# arduino-pro-mini_2-way-switches_v0_2_1.net
KiCad netlist of a schematic drawn in EAGLE
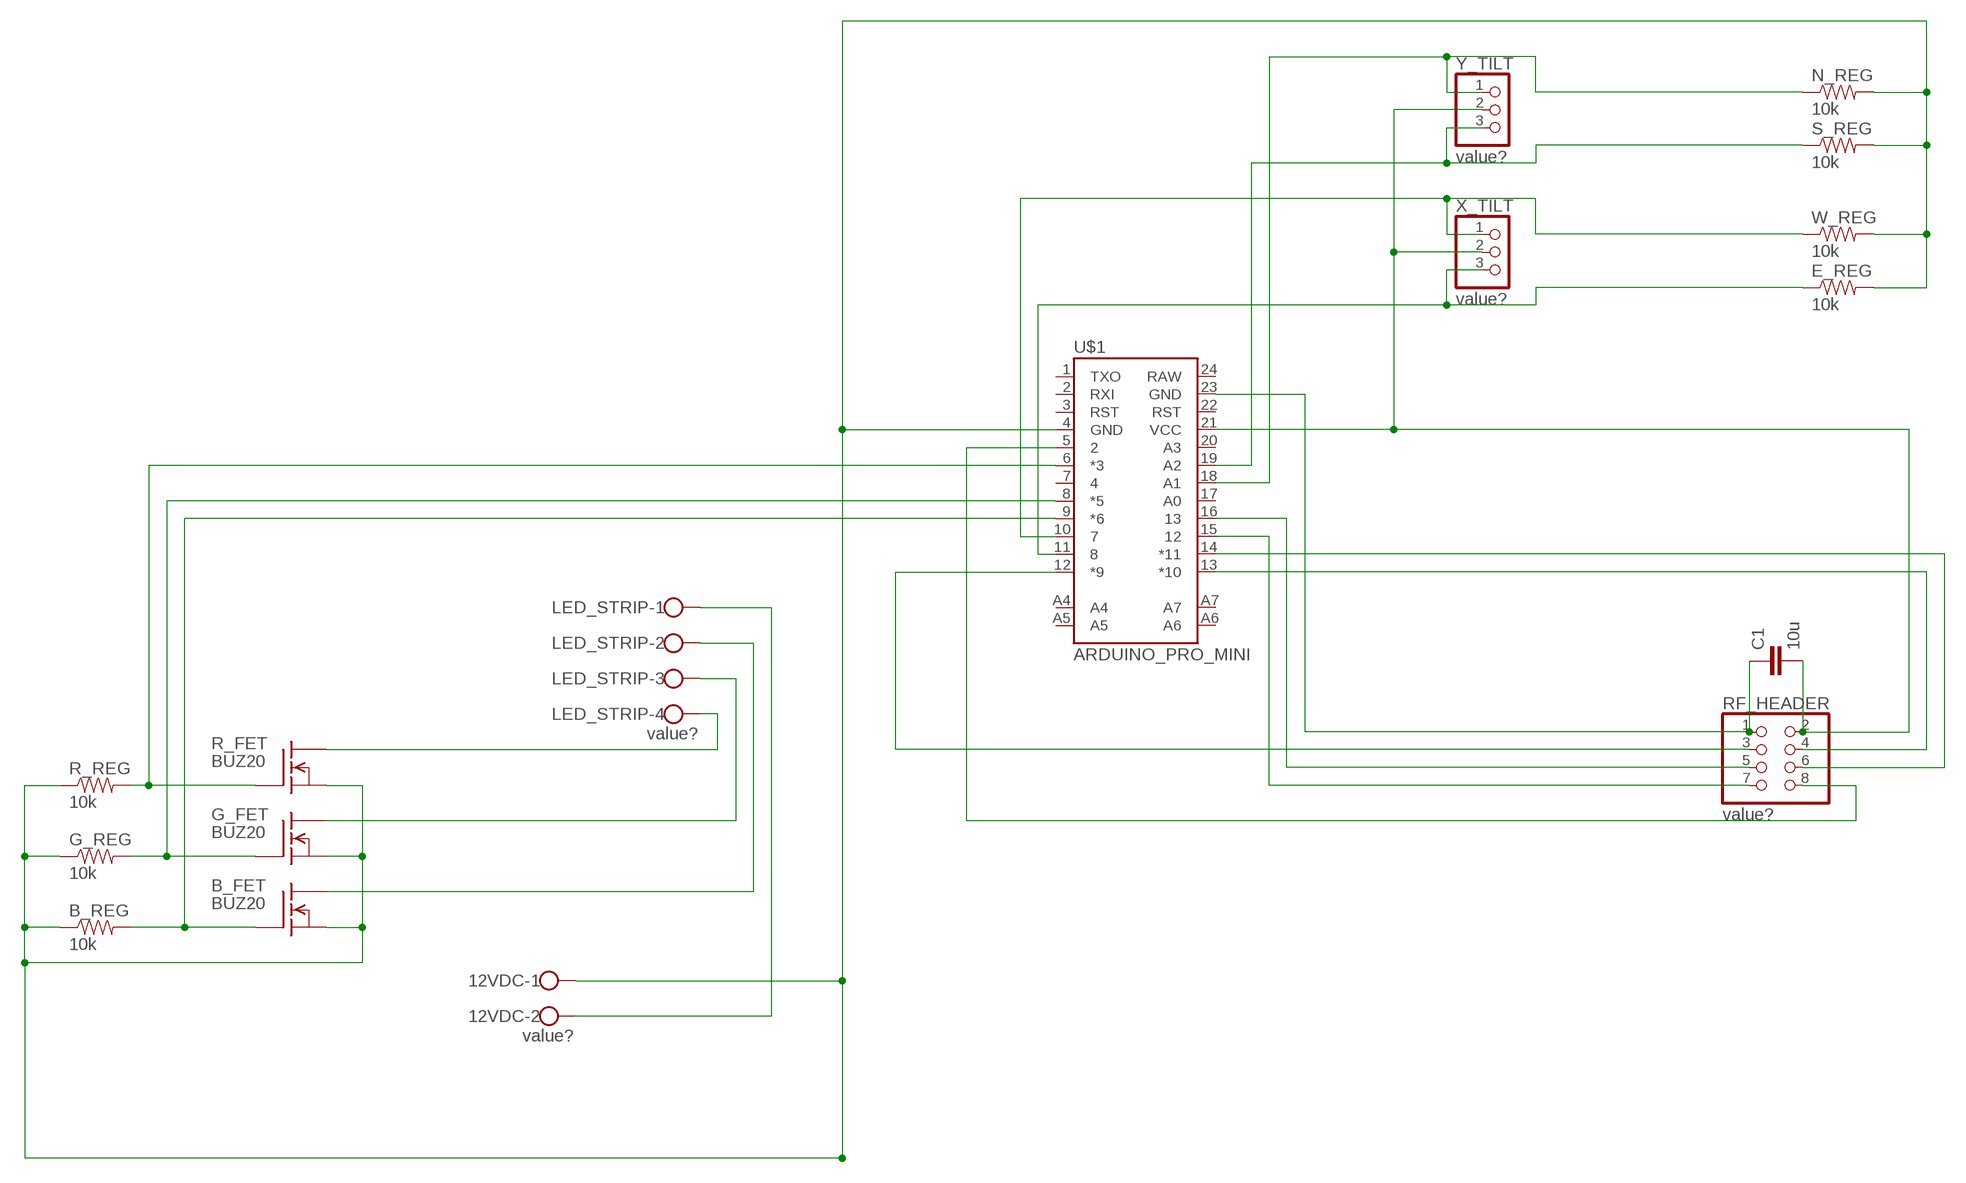
[diagram p0: schematic, sheet 1]

(export (version "E")
  (design (tool "Eeschema 10.0.6"))
  (components
    (comp (ref "12VDC")
      (value "value?")
      (footprint "eagle-import:W237-102")
      (fields (field (name "MPN") "237-102"))
      (libsource (lib "eagle-import") (part "W237-102"))
    )
    (comp (ref "B_FET")
      (value "BUZ20")
      (footprint "eagle-import:TO220")
      (libsource (lib "eagle-import") (part "BUZ20"))
    )
    (comp (ref "B_REG")
      (value "10k")
      (footprint "eagle-import:AXIAL-0.4")
      (libsource (lib "eagle-import") (part "RESISTORPTH-1/4W"))
    )
    (comp (ref "C1")
      (value "10u")
      (footprint "eagle-import:CAP-PTH-SMALL")
      (libsource (lib "eagle-import") (part "CAPPTH"))
    )
    (comp (ref "E_REG")
      (value "10k")
      (footprint "eagle-import:AXIAL-0.4")
      (libsource (lib "eagle-import") (part "RESISTORPTH-1/4W"))
    )
    (comp (ref "G_FET")
      (value "BUZ20")
      (footprint "eagle-import:TO220")
      (libsource (lib "eagle-import") (part "BUZ20"))
    )
    (comp (ref "G_REG")
      (value "10k")
      (footprint "eagle-import:AXIAL-0.4")
      (libsource (lib "eagle-import") (part "RESISTORPTH-1/4W"))
    )
    (comp (ref "LED_STRIP")
      (value "value?")
      (footprint "eagle-import:W237-4")
      (libsource (lib "eagle-import") (part "W237-4"))
    )
    (comp (ref "N_REG")
      (value "10k")
      (footprint "eagle-import:AXIAL-0.4")
      (libsource (lib "eagle-import") (part "RESISTORPTH-1/4W"))
    )
    (comp (ref "RF_HEADER")
      (value "value?")
      (footprint "eagle-import:2X04")
      (libsource (lib "eagle-import") (part "PINHD-2X4"))
    )
    (comp (ref "R_FET")
      (value "BUZ20")
      (footprint "eagle-import:TO220")
      (libsource (lib "eagle-import") (part "BUZ20"))
    )
    (comp (ref "R_REG")
      (value "10k")
      (footprint "eagle-import:AXIAL-0.4")
      (libsource (lib "eagle-import") (part "RESISTORPTH-1/4W"))
    )
    (comp (ref "S_REG")
      (value "10k")
      (footprint "eagle-import:AXIAL-0.4")
      (libsource (lib "eagle-import") (part "RESISTORPTH-1/4W"))
    )
    (comp (ref "U$1")
      (value "ARDUINO_PRO_MINI")
      (footprint "eagle-import:ARDUINO_PRO_MINI")
      (libsource (lib "eagle-import") (part "ARDUINO_PRO_MINI"))
    )
    (comp (ref "W_REG")
      (value "10k")
      (footprint "eagle-import:AXIAL-0.4")
      (libsource (lib "eagle-import") (part "RESISTORPTH-1/4W"))
    )
    (comp (ref "X_TILT")
      (value "value?")
      (footprint "eagle-import:1X03")
      (libsource (lib "eagle-import") (part "PINHD-1X3"))
    )
    (comp (ref "Y_TILT")
      (value "value?")
      (footprint "eagle-import:1X03")
      (libsource (lib "eagle-import") (part "PINHD-1X3"))
    )
  )
  (nets
    (net (code "1") (name "Net-(12VDCA-KL)") (class "Default")
      (node (ref "12VDC") (pin "1") (pinfunction "KL_1") (pintype "passive"))
      (node (ref "B_FET") (pin "3") (pinfunction "S_3") (pintype "passive"))
      (node (ref "B_REG") (pin "P$1") (pinfunction "1_P$1") (pintype "passive"))
      (node (ref "E_REG") (pin "P$2") (pinfunction "2_P$2") (pintype "passive"))
      (node (ref "G_FET") (pin "3") (pinfunction "S_3") (pintype "passive"))
      (node (ref "G_REG") (pin "P$1") (pinfunction "1_P$1") (pintype "passive"))
      (node (ref "N_REG") (pin "P$2") (pinfunction "2_P$2") (pintype "passive"))
      (node (ref "R_FET") (pin "3") (pinfunction "S_3") (pintype "passive"))
      (node (ref "R_REG") (pin "P$1") (pinfunction "1_P$1") (pintype "passive"))
      (node (ref "S_REG") (pin "P$2") (pinfunction "2_P$2") (pintype "passive"))
      (node (ref "U$1") (pin "4") (pinfunction "GND_4") (pintype "bidirectional"))
      (node (ref "W_REG") (pin "P$2") (pinfunction "2_P$2") (pintype "passive"))
    )
    (net (code "2") (name "Net-(12VDCB-KL)") (class "Default")
      (node (ref "12VDC") (pin "2") (pinfunction "KL_2") (pintype "passive"))
      (node (ref "LED_STRIP") (pin "1") (pinfunction "KL_1") (pintype "passive"))
    )
    (net (code "3") (name "Net-(B_FET-D)") (class "Default")
      (node (ref "B_FET") (pin "2") (pinfunction "D_2") (pintype "passive"))
      (node (ref "LED_STRIP") (pin "2") (pinfunction "KL_2") (pintype "passive"))
    )
    (net (code "4") (name "Net-(B_FET-G)") (class "Default")
      (node (ref "B_FET") (pin "1") (pinfunction "G_1") (pintype "passive"))
      (node (ref "B_REG") (pin "P$2") (pinfunction "2_P$2") (pintype "passive"))
      (node (ref "U$1") (pin "9") (pinfunction "*6_9") (pintype "bidirectional"))
    )
    (net (code "5") (name "Net-(C1-Pad1)") (class "Default")
      (node (ref "C1") (pin "1") (pinfunction "1_1") (pintype "passive"))
      (node (ref "RF_HEADER") (pin "1") (pinfunction "1_1") (pintype "passive"))
      (node (ref "U$1") (pin "23") (pinfunction "GND_23") (pintype "bidirectional"))
    )
    (net (code "6") (name "Net-(E_REG-1)") (class "Default")
      (node (ref "E_REG") (pin "P$1") (pinfunction "1_P$1") (pintype "passive"))
      (node (ref "U$1") (pin "11") (pinfunction "8_11") (pintype "bidirectional"))
      (node (ref "X_TILT") (pin "3") (pinfunction "3_3") (pintype "passive"))
    )
    (net (code "7") (name "Net-(G_FET-D)") (class "Default")
      (node (ref "G_FET") (pin "2") (pinfunction "D_2") (pintype "passive"))
      (node (ref "LED_STRIP") (pin "3") (pinfunction "KL_3") (pintype "passive"))
    )
    (net (code "8") (name "Net-(G_FET-G)") (class "Default")
      (node (ref "G_FET") (pin "1") (pinfunction "G_1") (pintype "passive"))
      (node (ref "G_REG") (pin "P$2") (pinfunction "2_P$2") (pintype "passive"))
      (node (ref "U$1") (pin "8") (pinfunction "*5_8") (pintype "bidirectional"))
    )
    (net (code "9") (name "Net-(LED_STRIPD-KL)") (class "Default")
      (node (ref "LED_STRIP") (pin "4") (pinfunction "KL_4") (pintype "passive"))
      (node (ref "R_FET") (pin "2") (pinfunction "D_2") (pintype "passive"))
    )
    (net (code "10") (name "Net-(N_REG-1)") (class "Default")
      (node (ref "N_REG") (pin "P$1") (pinfunction "1_P$1") (pintype "passive"))
      (node (ref "U$1") (pin "18") (pinfunction "A1_18") (pintype "bidirectional"))
      (node (ref "Y_TILT") (pin "1") (pinfunction "1_1") (pintype "passive"))
    )
    (net (code "11") (name "Net-(R_FET-G)") (class "Default")
      (node (ref "R_FET") (pin "1") (pinfunction "G_1") (pintype "passive"))
      (node (ref "R_REG") (pin "P$2") (pinfunction "2_P$2") (pintype "passive"))
      (node (ref "U$1") (pin "6") (pinfunction "*3_6") (pintype "bidirectional"))
    )
    (net (code "12") (name "Net-(S_REG-1)") (class "Default")
      (node (ref "S_REG") (pin "P$1") (pinfunction "1_P$1") (pintype "passive"))
      (node (ref "U$1") (pin "19") (pinfunction "A2_19") (pintype "bidirectional"))
      (node (ref "Y_TILT") (pin "3") (pinfunction "3_3") (pintype "passive"))
    )
    (net (code "13") (name "Net-(U$1-*9)") (class "Default")
      (node (ref "RF_HEADER") (pin "3") (pinfunction "3_3") (pintype "passive"))
      (node (ref "U$1") (pin "12") (pinfunction "*9_12") (pintype "bidirectional"))
    )
    (net (code "14") (name "Net-(U$1-*10)") (class "Default")
      (node (ref "RF_HEADER") (pin "4") (pinfunction "4_4") (pintype "passive"))
      (node (ref "U$1") (pin "13") (pinfunction "*10_13") (pintype "bidirectional"))
    )
    (net (code "15") (name "Net-(U$1-*11)") (class "Default")
      (node (ref "RF_HEADER") (pin "6") (pinfunction "6_6") (pintype "passive"))
      (node (ref "U$1") (pin "14") (pinfunction "*11_14") (pintype "bidirectional"))
    )
    (net (code "16") (name "Net-(U$1-2)") (class "Default")
      (node (ref "RF_HEADER") (pin "8") (pinfunction "8_8") (pintype "passive"))
      (node (ref "U$1") (pin "5") (pinfunction "2_5") (pintype "bidirectional"))
    )
    (net (code "17") (name "Net-(U$1-7)") (class "Default")
      (node (ref "U$1") (pin "10") (pinfunction "7_10") (pintype "bidirectional"))
      (node (ref "W_REG") (pin "P$1") (pinfunction "1_P$1") (pintype "passive"))
      (node (ref "X_TILT") (pin "1") (pinfunction "1_1") (pintype "passive"))
    )
    (net (code "18") (name "Net-(U$1-12)") (class "Default")
      (node (ref "RF_HEADER") (pin "7") (pinfunction "7_7") (pintype "passive"))
      (node (ref "U$1") (pin "15") (pinfunction "12_15") (pintype "bidirectional"))
    )
    (net (code "19") (name "Net-(U$1-13)") (class "Default")
      (node (ref "RF_HEADER") (pin "5") (pinfunction "5_5") (pintype "passive"))
      (node (ref "U$1") (pin "16") (pinfunction "13_16") (pintype "bidirectional"))
    )
    (net (code "20") (name "Net-(U$1-VCC)") (class "Default")
      (node (ref "C1") (pin "2") (pinfunction "2_2") (pintype "passive"))
      (node (ref "RF_HEADER") (pin "2") (pinfunction "2_2") (pintype "passive"))
      (node (ref "U$1") (pin "21") (pinfunction "VCC_21") (pintype "bidirectional"))
      (node (ref "X_TILT") (pin "2") (pinfunction "2_2") (pintype "passive"))
      (node (ref "Y_TILT") (pin "2") (pinfunction "2_2") (pintype "passive"))
    )
    (net (code "21") (name "unconnected-(U$1-4-Pad7)") (class "Default")
      (node (ref "U$1") (pin "7") (pinfunction "4_7") (pintype "bidirectional"))
    )
    (net (code "22") (name "unconnected-(U$1-A0-Pad17)") (class "Default")
      (node (ref "U$1") (pin "17") (pinfunction "A0_17") (pintype "bidirectional"))
    )
    (net (code "23") (name "unconnected-(U$1-A3-Pad20)") (class "Default")
      (node (ref "U$1") (pin "20") (pinfunction "A3_20") (pintype "bidirectional"))
    )
    (net (code "24") (name "unconnected-(U$1-PadA4)") (class "Default")
      (node (ref "U$1") (pin "A4") (pinfunction "A4_A4") (pintype "bidirectional"))
    )
    (net (code "25") (name "unconnected-(U$1-PadA5)") (class "Default")
      (node (ref "U$1") (pin "A5") (pinfunction "A5_A5") (pintype "bidirectional"))
    )
    (net (code "26") (name "unconnected-(U$1-PadA6)") (class "Default")
      (node (ref "U$1") (pin "A6") (pinfunction "A6_A6") (pintype "bidirectional"))
    )
    (net (code "27") (name "unconnected-(U$1-PadA7)") (class "Default")
      (node (ref "U$1") (pin "A7") (pinfunction "A7_A7") (pintype "bidirectional"))
    )
    (net (code "28") (name "unconnected-(U$1-RAW-Pad24)") (class "Default")
      (node (ref "U$1") (pin "24") (pinfunction "RAW_24") (pintype "bidirectional"))
    )
    (net (code "29") (name "unconnected-(U$1-RST-Pad3)") (class "Default")
      (node (ref "U$1") (pin "3") (pinfunction "RST_3") (pintype "bidirectional"))
    )
    (net (code "30") (name "unconnected-(U$1-RST-Pad22)") (class "Default")
      (node (ref "U$1") (pin "22") (pinfunction "RST_22") (pintype "bidirectional"))
    )
    (net (code "31") (name "unconnected-(U$1-RXI-Pad2)") (class "Default")
      (node (ref "U$1") (pin "2") (pinfunction "RXI_2") (pintype "bidirectional"))
    )
    (net (code "32") (name "unconnected-(U$1-TXO-Pad1)") (class "Default")
      (node (ref "U$1") (pin "1") (pinfunction "TXO_1") (pintype "bidirectional"))
    )
  )
)
